# 15_MicroSD_Card.net
KiCad netlist of a schematic drawn in Altium Designer
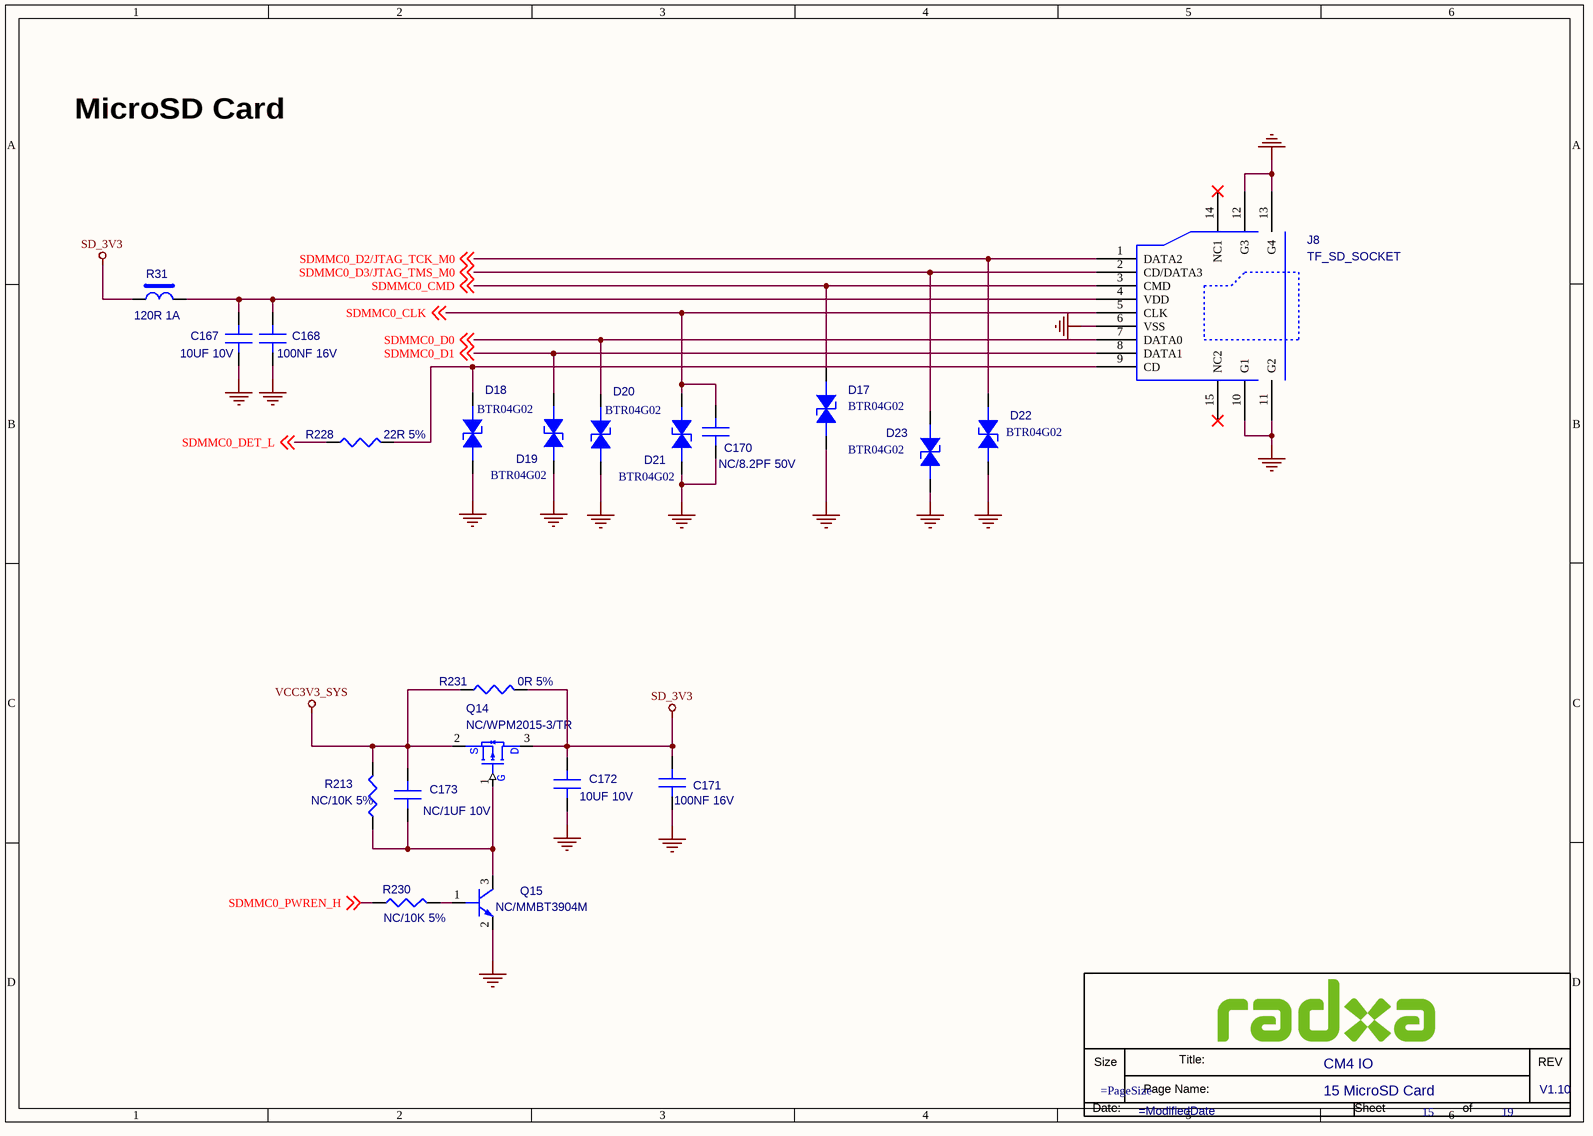
[diagram p0: 15 MicroSD Card.SchDoc]

(export (version "E")
  (design (tool "Eeschema 10.0.6"))
  (components
    (comp (ref "C167")
      (value "10UF 10V")
      (footprint "C0603")
      (description "SMD  0603  10UF  10V  X5R  ±10%  ROHS")
      (fields (field (name "PART NUMBER") "A1C01.00270"))
      (libsource (lib "*") (part "C"))
    )
    (comp (ref "C168")
      (value "100NF 16V")
      (footprint "C0201")
      (description "SMD  0201  100NF  16V  X5R  ±20%  ROHS")
      (fields (field (name "PART NUMBER") "A1C01.00099"))
      (libsource (lib "*") (part "C"))
    )
    (comp (ref "C170")
      (value "NC/8.2PF 50V")
      (footprint "C0201")
      (description "SMD  0201  8.2PF  50V  NPO  ±5%  ROHS")
      (fields (field (name "PART NUMBER") "A1C01.00147"))
      (libsource (lib "*") (part "C"))
    )
    (comp (ref "C171")
      (value "100NF 16V")
      (footprint "C0201")
      (description "SMD  0201  100NF  16V  X5R  ±20%  ROHS")
      (fields (field (name "PART NUMBER") "A1C01.00099"))
      (libsource (lib "*") (part "C"))
    )
    (comp (ref "C172")
      (value "10UF 10V")
      (footprint "C0603")
      (description "SMD  0603  10UF  10V  X5R  ±20%  ROHS")
      (fields (field (name "PART NUMBER") "A1C01.00075"))
      (libsource (lib "*") (part "C"))
    )
    (comp (ref "C173")
      (value "NC/1UF 10V")
      (footprint "C0201")
      (description "SMD  0201  1UF  10V  X5R  ±20%  ROHS")
      (fields (field (name "PART NUMBER") "A1C01.00081"))
      (libsource (lib "*") (part "C"))
    )
    (comp (ref "D17")
      (value "BTR04G02")
      (footprint "DFN1006-2L")
      (description "SMD  编带  0402  BTR04G02  B-tron  ROHS")
      (fields (field (name "PART NUMBER") "A1D02.00002"))
      (libsource (lib "*") (part "ESD"))
    )
    (comp (ref "D18")
      (value "BTR04G02")
      (footprint "DFN1006-2L")
      (description "SMD  编带  0402  BTR04G02  B-tron  ROHS")
      (fields (field (name "PART NUMBER") "A1D02.00002"))
      (libsource (lib "*") (part "ESD"))
    )
    (comp (ref "D19")
      (value "BTR04G02")
      (footprint "DFN1006-2L")
      (description "SMD  编带  0402  BTR04G02  B-tron  ROHS")
      (fields (field (name "PART NUMBER") "A1D02.00002"))
      (libsource (lib "*") (part "ESD"))
    )
    (comp (ref "D20")
      (value "BTR04G02")
      (footprint "DFN1006-2L")
      (description "SMD  编带  0402  BTR04G02  B-tron  ROHS")
      (fields (field (name "PART NUMBER") "A1D02.00002"))
      (libsource (lib "*") (part "ESD"))
    )
    (comp (ref "D21")
      (value "BTR04G02")
      (footprint "DFN1006-2L")
      (description "SMD  编带  0402  BTR04G02  B-tron  ROHS")
      (fields (field (name "PART NUMBER") "A1D02.00002"))
      (libsource (lib "*") (part "ESD"))
    )
    (comp (ref "D22")
      (value "BTR04G02")
      (footprint "DFN1006-2L")
      (description "SMD  编带  0402  BTR04G02  B-tron  ROHS")
      (fields (field (name "PART NUMBER") "A1D02.00002"))
      (libsource (lib "*") (part "ESD"))
    )
    (comp (ref "D23")
      (value "BTR04G02")
      (footprint "DFN1006-2L")
      (description "SMD  编带  0402  BTR04G02  B-tron  ROHS")
      (fields (field (name "PART NUMBER") "A1D02.00002"))
      (libsource (lib "*") (part "ESD"))
    )
    (comp (ref "J8")
      (value "TF_SD_SOCKET")
      (footprint "SD_SM9_1D1_15D75")
      (description "SMD  XKTF-N02-N  14.7*14.8*H1.95mm  9PIN  不锈钢  星坤  ROHS")
      (fields (field (name "PART NUMBER") "A1J09.00014"))
      (libsource (lib "*") (part "TF_SD_SOCKET"))
    )
    (comp (ref "Q14")
      (value "NC/WPM2015-3/TR")
      (footprint "SOT_23")
      (description "SMD编带  SOT-23  WPM2015-3/TR  P沟道  ROHS")
      (fields (field (name "PART NUMBER") "A1D01.00019"))
      (libsource (lib "*") (part "MOSFET_PNP"))
    )
    (comp (ref "Q15")
      (value "NC/MMBT3904M")
      (footprint "SOT_723")
      (description "SMD编带  SOT-723  MMBT3904M  NPN  ROHS")
      (fields
        (field (name "MANUFACTURER") "长电")
        (field (name "PART NUMBER") "A1D01.00002")
        (field (name "CREATED BY") "JJJ")
      )
      (libsource (lib "*") (part "NPN"))
    )
    (comp (ref "R31")
      (value "120R 1A")
      (footprint "FB0201")
      (description "SMD  0201  FB120R  1A  MPZ0603S121HT000  ±25%  ROHS")
      (fields (field (name "PART NUMBER") "A1L09.00033"))
      (libsource (lib "*") (part "BEAD"))
    )
    (comp (ref "R213")
      (value "NC/10K 5%")
      (footprint "R0402")
      (description "SMD  0201  10K  1/20W  ±5%  ROHS")
      (fields (field (name "PART NUMBER") "A1R01.00012"))
      (libsource (lib "*") (part "R"))
    )
    (comp (ref "R228")
      (value "22R 5%")
      (footprint "R0402")
      (description "SMD  0201  22R  1/20W  ±5%  ROHS")
      (fields (field (name "PART NUMBER") "A1R01.00024"))
      (libsource (lib "*") (part "R"))
    )
    (comp (ref "R230")
      (value "NC/10K 5%")
      (footprint "R0402")
      (description "SMD  0201  10K  1/20W  ±5%  ROHS")
      (fields (field (name "PART NUMBER") "A1R01.00012"))
      (libsource (lib "*") (part "R"))
    )
    (comp (ref "R231")
      (value "0R 5%")
      (footprint "R0402")
      (description "SMD  0201  0R  1/20W  ±5%  ROHS")
      (fields (field (name "PART NUMBER") "A1R01.00027"))
      (libsource (lib "*") (part "R"))
    )
  )
  (nets
    (net (code "1") (name "GND") (class "Default")
      (node (ref "C167") (pin "2") (pinfunction "B_2") (pintype "passive"))
      (node (ref "C168") (pin "2") (pinfunction "B_2") (pintype "passive"))
      (node (ref "C170") (pin "2") (pinfunction "B_2") (pintype "passive"))
      (node (ref "C171") (pin "2") (pinfunction "B_2") (pintype "passive"))
      (node (ref "C172") (pin "2") (pinfunction "B_2") (pintype "passive"))
      (node (ref "D17") (pin "1") (pinfunction "ANODE_1") (pintype "passive"))
      (node (ref "D18") (pin "1") (pinfunction "ANODE_1") (pintype "passive"))
      (node (ref "D19") (pin "1") (pinfunction "ANODE_1") (pintype "passive"))
      (node (ref "D20") (pin "1") (pinfunction "ANODE_1") (pintype "passive"))
      (node (ref "D21") (pin "1") (pinfunction "ANODE_1") (pintype "passive"))
      (node (ref "D22") (pin "1") (pinfunction "ANODE_1") (pintype "passive"))
      (node (ref "D23") (pin "1") (pinfunction "ANODE_1") (pintype "passive"))
      (node (ref "J8") (pin "10") (pinfunction "G1_10") (pintype "passive"))
      (node (ref "J8") (pin "11") (pinfunction "G2_11") (pintype "passive"))
      (node (ref "J8") (pin "12") (pinfunction "G3_12") (pintype "passive"))
      (node (ref "J8") (pin "13") (pinfunction "G4_13") (pintype "passive"))
      (node (ref "J8") (pin "6") (pinfunction "VSS_6") (pintype "passive"))
      (node (ref "Q15") (pin "2") (pinfunction "EMITTER_2") (pintype "passive"))
    )
    (net (code "2") (name "Net-(C167-A)") (class "Default")
      (node (ref "C167") (pin "1") (pinfunction "A_1") (pintype "passive"))
      (node (ref "C168") (pin "1") (pinfunction "A_1") (pintype "passive"))
      (node (ref "J8") (pin "4") (pinfunction "VDD_4") (pintype "passive"))
      (node (ref "R31") (pin "2") (pinfunction "2_2") (pintype "passive"))
    )
    (net (code "3") (name "Net-(C173-B)") (class "Default")
      (node (ref "C173") (pin "2") (pinfunction "B_2") (pintype "passive"))
      (node (ref "Q14") (pin "1") (pinfunction "G_1") (pintype "input"))
      (node (ref "Q15") (pin "3") (pinfunction "COLLECTOR_3") (pintype "passive"))
      (node (ref "R213") (pin "1") (pinfunction "1_1") (pintype "passive"))
    )
    (net (code "4") (name "Net-(D18-CATHODE)") (class "Default")
      (node (ref "D18") (pin "2") (pinfunction "CATHODE_2") (pintype "passive"))
      (node (ref "J8") (pin "9") (pinfunction "CD_9") (pintype "passive"))
      (node (ref "R228") (pin "2") (pinfunction "2_2") (pintype "passive"))
    )
    (net (code "5") (name "Net-(Q15-BASE)") (class "Default")
      (node (ref "Q15") (pin "1") (pinfunction "BASE_1") (pintype "passive"))
      (node (ref "R230") (pin "2") (pinfunction "2_2") (pintype "passive"))
    )
    (net (code "6") (name "SDMMC0_CLK") (class "Default")
      (node (ref "C170") (pin "1") (pinfunction "A_1") (pintype "passive"))
      (node (ref "D21") (pin "2") (pinfunction "CATHODE_2") (pintype "passive"))
      (node (ref "J8") (pin "5") (pinfunction "CLK_5") (pintype "passive"))
    )
    (net (code "7") (name "SDMMC0_CMD") (class "Default")
      (node (ref "D17") (pin "2") (pinfunction "CATHODE_2") (pintype "passive"))
      (node (ref "J8") (pin "3") (pinfunction "CMD_3") (pintype "passive"))
    )
    (net (code "8") (name "SDMMC0_D0") (class "Default")
      (node (ref "D20") (pin "2") (pinfunction "CATHODE_2") (pintype "passive"))
      (node (ref "J8") (pin "7") (pinfunction "DATA0_7") (pintype "passive"))
    )
    (net (code "9") (name "SDMMC0_D1") (class "Default")
      (node (ref "D19") (pin "2") (pinfunction "CATHODE_2") (pintype "passive"))
      (node (ref "J8") (pin "8") (pinfunction "DATA1_8") (pintype "passive"))
    )
    (net (code "10") (name "SDMMC0_D2{slash}JTAG_TCK_M0") (class "Default")
      (node (ref "D22") (pin "2") (pinfunction "CATHODE_2") (pintype "passive"))
      (node (ref "J8") (pin "1") (pinfunction "DATA2_1") (pintype "passive"))
    )
    (net (code "11") (name "SDMMC0_D3{slash}JTAG_TMS_M0") (class "Default")
      (node (ref "D23") (pin "2") (pinfunction "CATHODE_2") (pintype "passive"))
      (node (ref "J8") (pin "2") (pinfunction "CD/DATA3_2") (pintype "passive"))
    )
    (net (code "12") (name "SDMMC0_DET_L") (class "Default")
      (node (ref "R228") (pin "1") (pinfunction "1_1") (pintype "passive"))
    )
    (net (code "13") (name "SDMMC0_PWREN_H") (class "Default")
      (node (ref "R230") (pin "1") (pinfunction "1_1") (pintype "passive"))
    )
    (net (code "14") (name "SD_3V3") (class "Default")
      (node (ref "C171") (pin "1") (pinfunction "A_1") (pintype "passive"))
      (node (ref "C172") (pin "1") (pinfunction "A_1") (pintype "passive"))
      (node (ref "Q14") (pin "3") (pinfunction "D_3") (pintype "passive"))
      (node (ref "R231") (pin "2") (pinfunction "2_2") (pintype "passive"))
      (node (ref "R31") (pin "1") (pinfunction "1_1") (pintype "passive"))
    )
    (net (code "15") (name "VCC3V3_SYS") (class "Default")
      (node (ref "C173") (pin "1") (pinfunction "A_1") (pintype "passive"))
      (node (ref "Q14") (pin "2") (pinfunction "S_2") (pintype "passive"))
      (node (ref "R213") (pin "2") (pinfunction "2_2") (pintype "passive"))
      (node (ref "R231") (pin "1") (pinfunction "1_1") (pintype "passive"))
    )
    (net (code "16") (name "unconnected-(J8-NC1-Pad14)") (class "Default")
      (node (ref "J8") (pin "14") (pinfunction "NC1_14") (pintype "passive+no_connect"))
    )
    (net (code "17") (name "unconnected-(J8-NC2-Pad15)") (class "Default")
      (node (ref "J8") (pin "15") (pinfunction "NC2_15") (pintype "passive+no_connect"))
    )
  )
)
